# ADC.net
KiCad netlist of a schematic drawn in Altium Designer
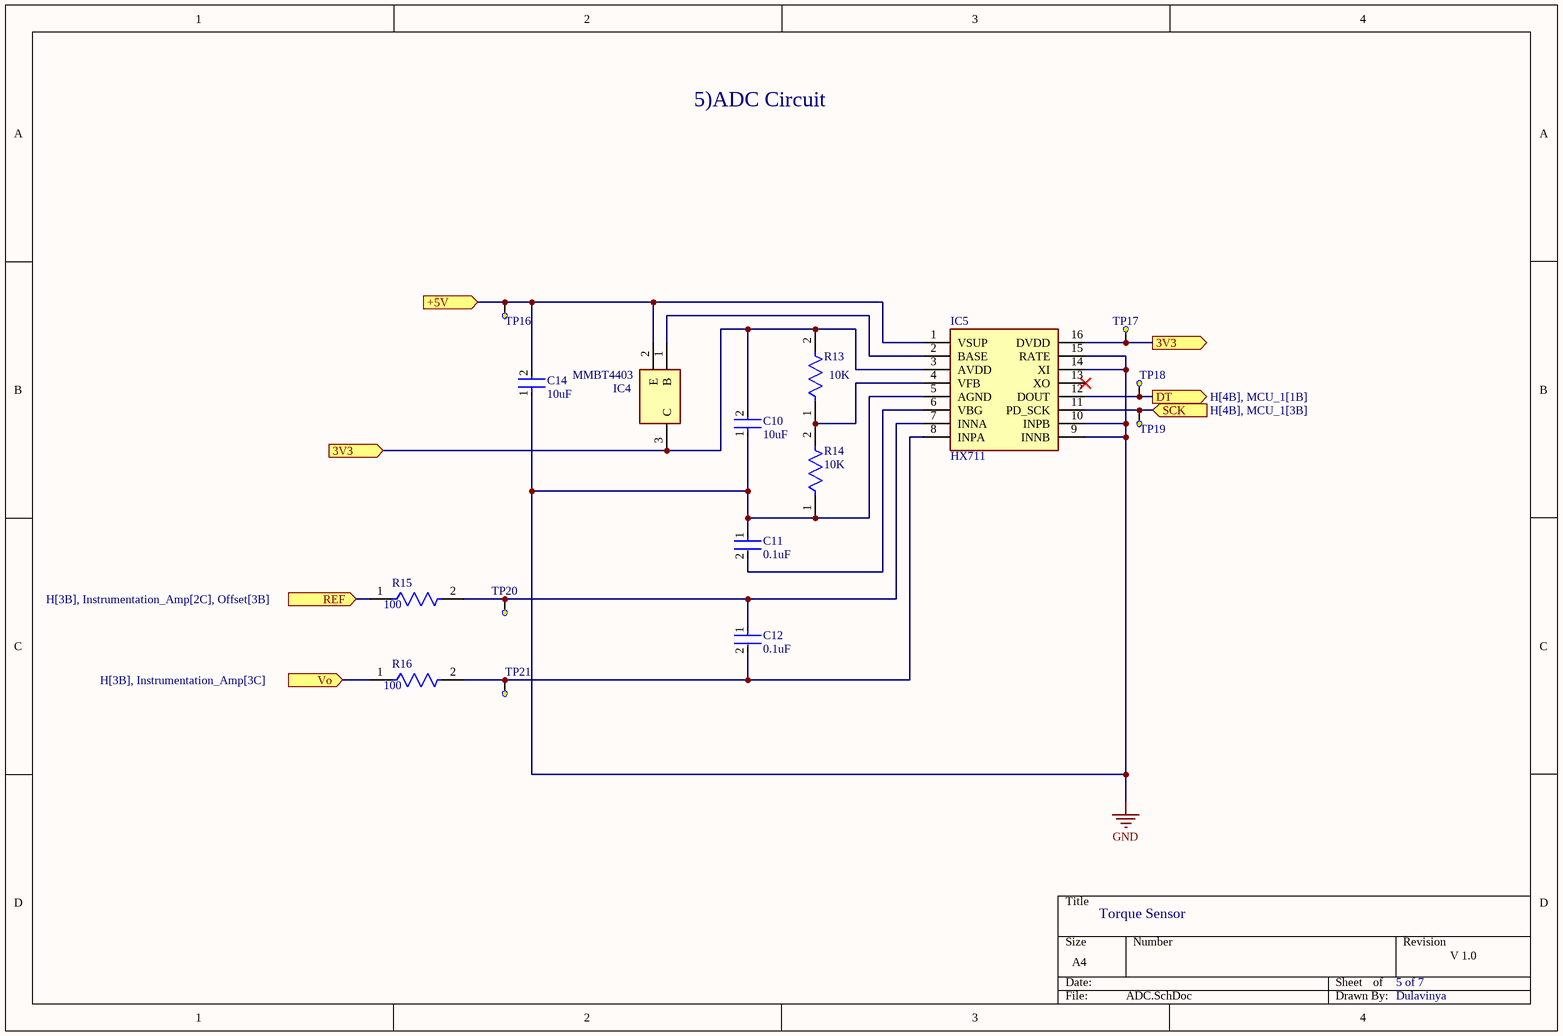
[diagram p0: ADC.SchDoc]

(export (version "E")
  (design (tool "Eeschema 10.0.6"))
  (components
    (comp (ref "C10")
      (value "10uF")
      (footprint "FP-CL05A106MP5NUNC-MFG")
      (description "CAP CER 10UF 10V X5R 0402")
      (fields
        (field (name "OCTOPART") "https://octopart.com/cl05a106mp5nunc-samsung-22457395")
        (field (name "TOLERANCE") "20%")
      )
      (libsource (lib "Altium Content Vault") (part "b4654b650e69147ec39a6b967a45e02"))
    )
    (comp (ref "C11")
      (value "0.1uF")
      (footprint "FP-C0402-BB-MFG")
      (description "CAP CER 0.1UF 16V X7R 0402")
      (fields
        (field (name "TOLERANCE") "0.1")
        (field (name "OCTOPART") "https://octopart.com/c0402c104k4ractu-kemet-94158")
      )
      (libsource (lib "Altium Content Vault") (part "b4654b650e69147ec39a6b967a45e02"))
    )
    (comp (ref "C12")
      (value "0.1uF")
      (footprint "FP-C0402-BB-MFG")
      (description "CAP CER 0.1UF 16V X7R 0402")
      (fields
        (field (name "TOLERANCE") "0.1")
        (field (name "OCTOPART") "https://octopart.com/c0402c104k4ractu-kemet-94158")
      )
      (libsource (lib "Altium Content Vault") (part "b4654b650e69147ec39a6b967a45e02"))
    )
    (comp (ref "C14")
      (value "10uF")
      (footprint "FP-CL05A106MP5NUNC-MFG")
      (description "CAP CER 10UF 10V X5R 0402")
      (fields
        (field (name "OCTOPART") "https://octopart.com/cl05a106mp5nunc-samsung-22457395")
        (field (name "TOLERANCE") "20%")
      )
      (libsource (lib "Altium Content Vault") (part "b4654b650e69147ec39a6b967a45e02"))
    )
    (comp (ref "IC4")
      (value "MMBT4403")
      (footprint "SamacSys:SOT95P248X115-3N")
      (description "Integrated Circuit")
      (fields (field (name "MOUSER PART NUMBER") "637-MMBT4403"))
      (libsource (lib "*") (part "MMBT4403"))
    )
    (comp (ref "IC5")
      (value "HX711")
      (footprint "SamacSys:SOIC127P600X160-16N")
      (description "Integrated Circuit")
      (libsource (lib "*") (part "HX711"))
    )
    (comp (ref "R13")
      (value "10K")
      (footprint "FP-ERJ2R-MFG")
      (description "RES SMD 15K OHM 1% 1/10W 0402")
      (fields (field (name "TOLERANCE") "1%") (field (name "MANUFACTURER PART NUMBER") "ERJ-2RKF1502X"))
      (libsource (lib "Altium Content Vault") (part "1029c3af85768c4190bb7ad29bc67b5"))
    )
    (comp (ref "R14")
      (value "10K")
      (footprint "FP-ERJ2R-MFG")
      (description "RES SMD 15K OHM 1% 1/10W 0402")
      (fields (field (name "TOLERANCE") "1%") (field (name "MANUFACTURER PART NUMBER") "ERJ-2RKF1502X"))
      (libsource (lib "Altium Content Vault") (part "1029c3af85768c4190bb7ad29bc67b5"))
    )
    (comp (ref "R15")
      (value "100")
      (footprint "FP-ERJ2R-MFG")
      (description "RES SMD 15K OHM 1% 1/10W 0402")
      (fields (field (name "TOLERANCE") "1%") (field (name "MANUFACTURER PART NUMBER") "ERJ-2RKF1502X"))
      (libsource (lib "Altium Content Vault") (part "1029c3af85768c4190bb7ad29bc67b5"))
    )
    (comp (ref "R16")
      (value "100")
      (footprint "FP-ERJ2R-MFG")
      (description "RES SMD 15K OHM 1% 1/10W 0402")
      (fields (field (name "TOLERANCE") "1%") (field (name "MANUFACTURER PART NUMBER") "ERJ-2RKF1502X"))
      (libsource (lib "Altium Content Vault") (part "1029c3af85768c4190bb7ad29bc67b5"))
    )
    (comp (ref "TP16")
      (value "Test point")
      (footprint "Test_point")
      (libsource (lib "Schlib1") (part "test_point"))
    )
    (comp (ref "TP17")
      (value "Test point")
      (footprint "Test_point")
      (libsource (lib "Schlib1") (part "test_point"))
    )
    (comp (ref "TP18")
      (value "Test point")
      (footprint "Test_point")
      (libsource (lib "Schlib1") (part "test_point"))
    )
    (comp (ref "TP19")
      (value "Test point")
      (footprint "Test_point")
      (libsource (lib "Schlib1") (part "test_point"))
    )
    (comp (ref "TP20")
      (value "Test point")
      (footprint "Test_point")
      (libsource (lib "Schlib1") (part "test_point"))
    )
    (comp (ref "TP21")
      (value "Test point")
      (footprint "Test_point")
      (libsource (lib "Schlib1") (part "test_point"))
    )
  )
  (nets
    (net (code "1") (name "/+5V") (class "Default")
      (node (ref "C14") (pin "2") (pinfunction "2_2") (pintype "passive"))
      (node (ref "IC4") (pin "2") (pinfunction "E_2") (pintype "passive"))
      (node (ref "IC5") (pin "1") (pinfunction "VSUP_1") (pintype "passive"))
      (node (ref "TP16") (pin "TP?") (pinfunction "Test_point_TP?") (pintype "passive"))
    )
    (net (code "2") (name "/3V3") (class "Default")
      (node (ref "C10") (pin "2") (pinfunction "2_2") (pintype "passive"))
      (node (ref "IC4") (pin "3") (pinfunction "C_3") (pintype "passive"))
      (node (ref "IC5") (pin "16") (pinfunction "DVDD_16") (pintype "passive"))
      (node (ref "IC5") (pin "3") (pinfunction "AVDD_3") (pintype "passive"))
      (node (ref "R13") (pin "2") (pinfunction "2_2") (pintype "passive"))
      (node (ref "TP17") (pin "TP?") (pinfunction "Test_point_TP?") (pintype "passive"))
    )
    (net (code "3") (name "/DT") (class "Default")
      (node (ref "IC5") (pin "12") (pinfunction "DOUT_12") (pintype "passive"))
      (node (ref "TP18") (pin "TP?") (pinfunction "Test_point_TP?") (pintype "passive"))
    )
    (net (code "4") (name "/REF") (class "Default")
      (node (ref "R15") (pin "1") (pinfunction "1_1") (pintype "passive"))
    )
    (net (code "5") (name "/SCK") (class "Default")
      (node (ref "IC5") (pin "11") (pinfunction "PD_SCK_11") (pintype "passive"))
      (node (ref "TP19") (pin "TP?") (pinfunction "Test_point_TP?") (pintype "passive"))
    )
    (net (code "6") (name "/Vo") (class "Default")
      (node (ref "R16") (pin "1") (pinfunction "1_1") (pintype "passive"))
    )
    (net (code "7") (name "GND") (class "Default")
      (node (ref "C10") (pin "1") (pinfunction "1_1") (pintype "passive"))
      (node (ref "C11") (pin "1") (pinfunction "1_1") (pintype "passive"))
      (node (ref "C14") (pin "1") (pinfunction "1_1") (pintype "passive"))
      (node (ref "IC5") (pin "10") (pinfunction "INPB_10") (pintype "passive"))
      (node (ref "IC5") (pin "14") (pinfunction "XI_14") (pintype "passive"))
      (node (ref "IC5") (pin "15") (pinfunction "RATE_15") (pintype "passive"))
      (node (ref "IC5") (pin "5") (pinfunction "AGND_5") (pintype "passive"))
      (node (ref "IC5") (pin "9") (pinfunction "INNB_9") (pintype "passive"))
      (node (ref "R14") (pin "1") (pinfunction "1_1") (pintype "passive"))
    )
    (net (code "8") (name "Net-(IC4-B)") (class "Default")
      (node (ref "IC4") (pin "1") (pinfunction "B_1") (pintype "passive"))
      (node (ref "IC5") (pin "2") (pinfunction "BASE_2") (pintype "passive"))
    )
    (net (code "9") (name "Net-(IC5-INNA)") (class "Default")
      (node (ref "C12") (pin "1") (pinfunction "1_1") (pintype "passive"))
      (node (ref "IC5") (pin "7") (pinfunction "INNA_7") (pintype "passive"))
      (node (ref "R15") (pin "2") (pinfunction "2_2") (pintype "passive"))
      (node (ref "TP20") (pin "TP?") (pinfunction "Test_point_TP?") (pintype "passive"))
    )
    (net (code "10") (name "Net-(IC5-INPA)") (class "Default")
      (node (ref "C12") (pin "2") (pinfunction "2_2") (pintype "passive"))
      (node (ref "IC5") (pin "8") (pinfunction "INPA_8") (pintype "passive"))
      (node (ref "R16") (pin "2") (pinfunction "2_2") (pintype "passive"))
      (node (ref "TP21") (pin "TP?") (pinfunction "Test_point_TP?") (pintype "passive"))
    )
    (net (code "11") (name "Net-(IC5-VBG)") (class "Default")
      (node (ref "C11") (pin "2") (pinfunction "2_2") (pintype "passive"))
      (node (ref "IC5") (pin "6") (pinfunction "VBG_6") (pintype "passive"))
    )
    (net (code "12") (name "Net-(IC5-VFB)") (class "Default")
      (node (ref "IC5") (pin "4") (pinfunction "VFB_4") (pintype "passive"))
      (node (ref "R13") (pin "1") (pinfunction "1_1") (pintype "passive"))
      (node (ref "R14") (pin "2") (pinfunction "2_2") (pintype "passive"))
    )
    (net (code "13") (name "unconnected-(IC5-XO-Pad13)") (class "Default")
      (node (ref "IC5") (pin "13") (pinfunction "XO_13") (pintype "passive+no_connect"))
    )
  )
)
